# ADS1298-breakout.net
KiCad netlist of a schematic drawn in EAGLE
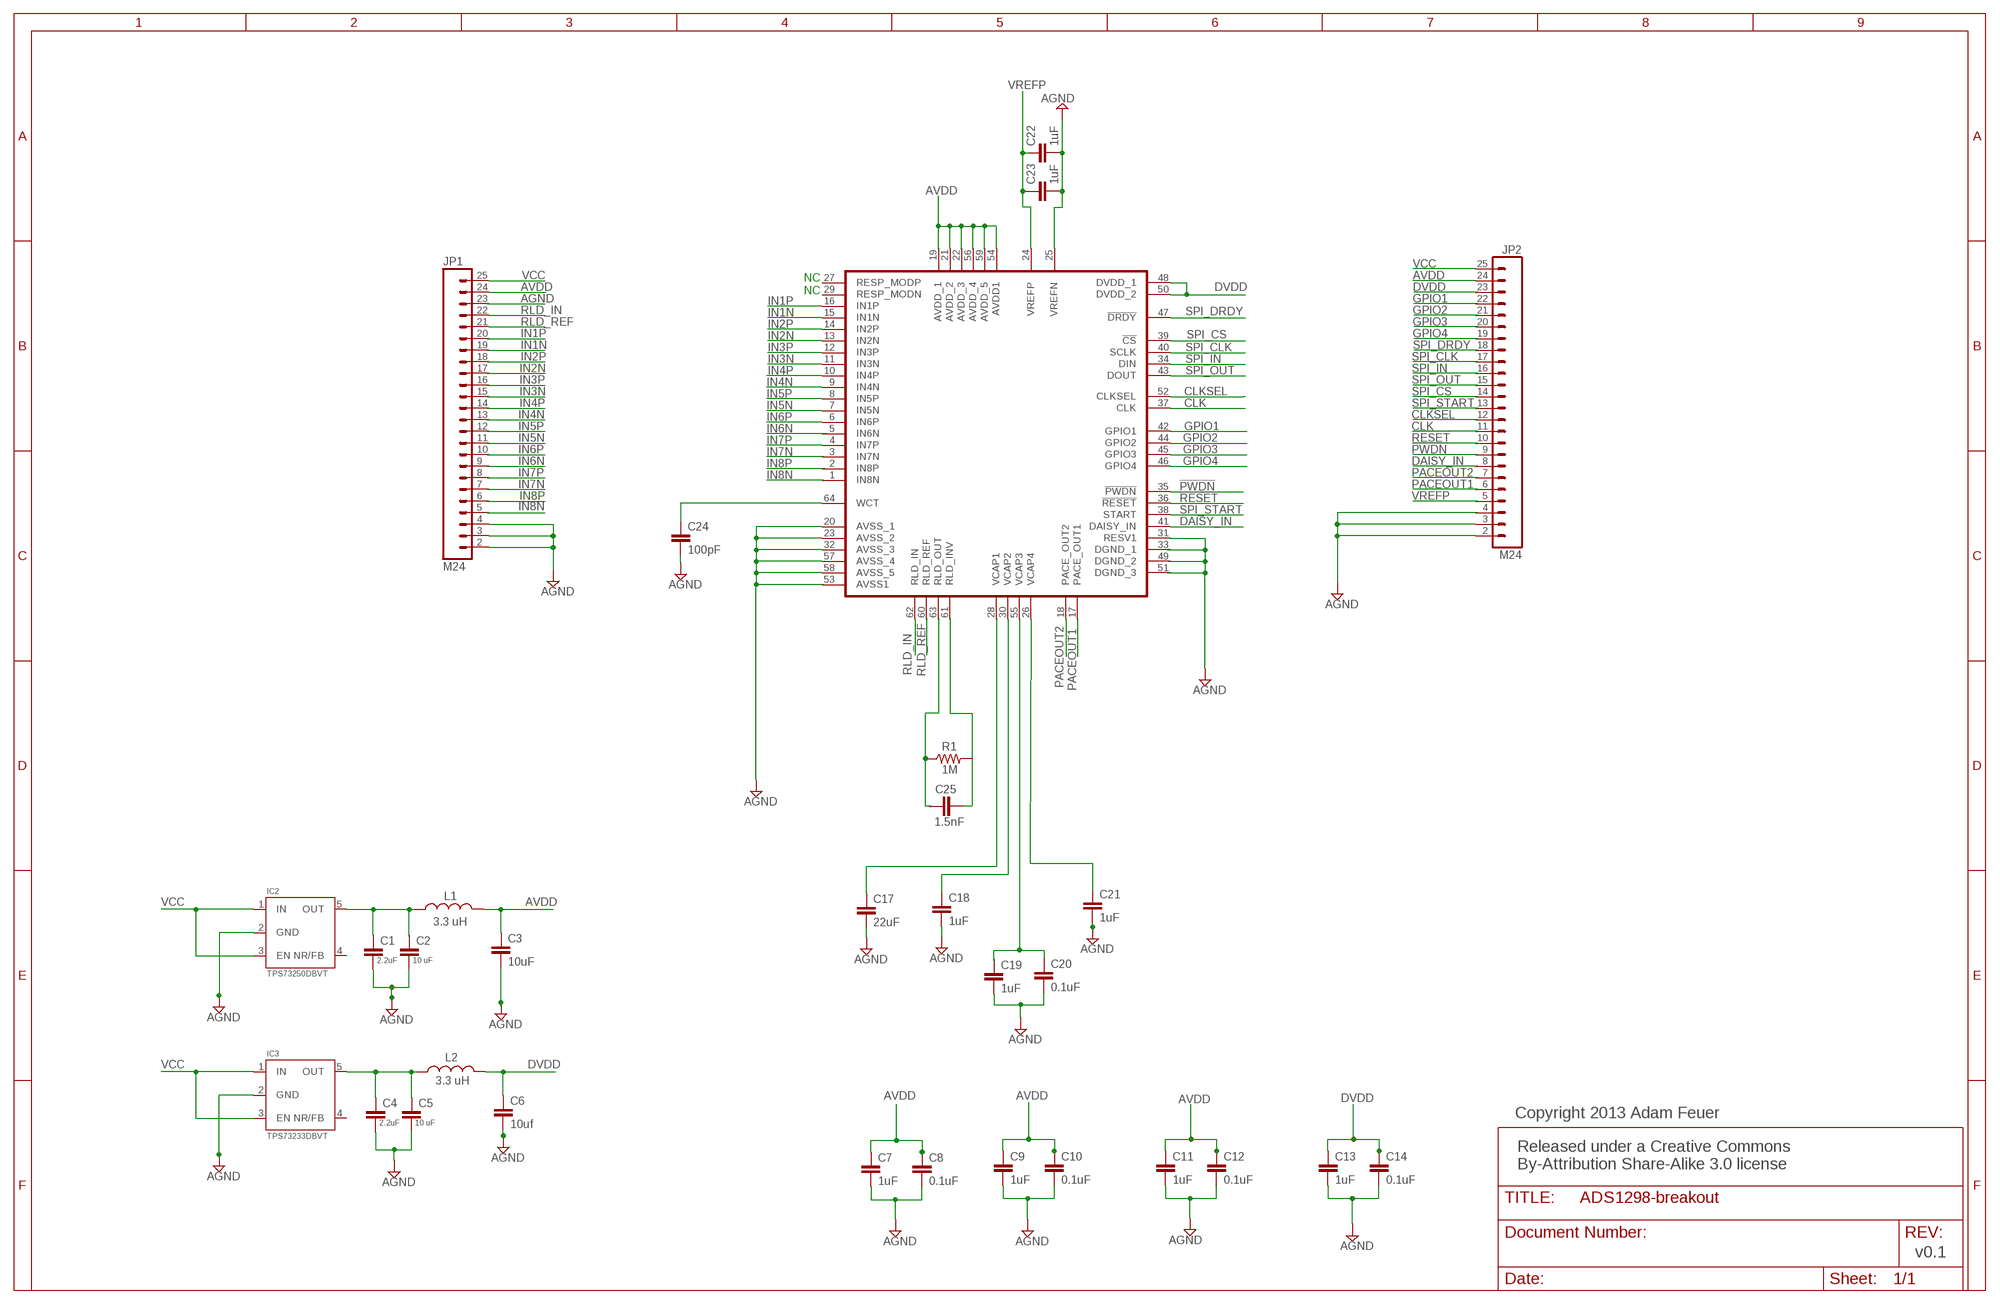
[diagram p0: schematic, sheet 1]

(export (version "E")
  (design (tool "Eeschema 10.0.6"))
  (components
    (comp (ref "C1")
      (value "2.2uF")
      (footprint "eagle-import:0603-CAP")
      (libsource (lib "eagle-import") (part "CAP0603-CAP"))
    )
    (comp (ref "C2")
      (value "10 uF")
      (footprint "eagle-import:0603-CAP")
      (libsource (lib "eagle-import") (part "CAP0603-CAP"))
    )
    (comp (ref "C3")
      (value "10uF")
      (footprint "eagle-import:0603-CAP")
      (libsource (lib "eagle-import") (part "CAP0603-CAP"))
    )
    (comp (ref "C4")
      (value "2.2uF")
      (footprint "eagle-import:0603-CAP")
      (libsource (lib "eagle-import") (part "CAP0603-CAP"))
    )
    (comp (ref "C5")
      (value "10 uF")
      (footprint "eagle-import:0603-CAP")
      (libsource (lib "eagle-import") (part "CAP0603-CAP"))
    )
    (comp (ref "C6")
      (value "10uf")
      (footprint "eagle-import:0603-CAP")
      (libsource (lib "eagle-import") (part "CAP0603-CAP"))
    )
    (comp (ref "C7")
      (value "1uF")
      (footprint "eagle-import:0603-CAP")
      (libsource (lib "eagle-import") (part "CAP0603-CAP"))
    )
    (comp (ref "C8")
      (value "0.1uF")
      (footprint "eagle-import:0603-CAP")
      (libsource (lib "eagle-import") (part "CAP0603-CAP"))
    )
    (comp (ref "C9")
      (value "1uF")
      (footprint "eagle-import:0603-CAP")
      (libsource (lib "eagle-import") (part "CAP0603-CAP"))
    )
    (comp (ref "C10")
      (value "0.1uF")
      (footprint "eagle-import:0603-CAP")
      (libsource (lib "eagle-import") (part "CAP0603-CAP"))
    )
    (comp (ref "C11")
      (value "1uF")
      (footprint "eagle-import:0603-CAP")
      (libsource (lib "eagle-import") (part "CAP0603-CAP"))
    )
    (comp (ref "C12")
      (value "0.1uF")
      (footprint "eagle-import:0603-CAP")
      (libsource (lib "eagle-import") (part "CAP0603-CAP"))
    )
    (comp (ref "C13")
      (value "1uF")
      (footprint "eagle-import:0603-CAP")
      (libsource (lib "eagle-import") (part "CAP0603-CAP"))
    )
    (comp (ref "C14")
      (value "0.1uF")
      (footprint "eagle-import:0603-CAP")
      (libsource (lib "eagle-import") (part "CAP0603-CAP"))
    )
    (comp (ref "C17")
      (value "22uF")
      (footprint "eagle-import:0603-CAP")
      (libsource (lib "eagle-import") (part "CAP0603-CAP"))
    )
    (comp (ref "C18")
      (value "1uF")
      (footprint "eagle-import:0603-CAP")
      (libsource (lib "eagle-import") (part "CAP0603-CAP"))
    )
    (comp (ref "C19")
      (value "1uF")
      (footprint "eagle-import:0603-CAP")
      (libsource (lib "eagle-import") (part "CAP0603-CAP"))
    )
    (comp (ref "C20")
      (value "0.1uF")
      (footprint "eagle-import:0603-CAP")
      (libsource (lib "eagle-import") (part "CAP0603-CAP"))
    )
    (comp (ref "C21")
      (value "1uF")
      (footprint "eagle-import:0603-CAP")
      (libsource (lib "eagle-import") (part "CAP0603-CAP"))
    )
    (comp (ref "C22")
      (value "1uF")
      (footprint "eagle-import:0603-CAP")
      (libsource (lib "eagle-import") (part "CAP0603-CAP"))
    )
    (comp (ref "C23")
      (value "1uF")
      (footprint "eagle-import:0603-CAP")
      (libsource (lib "eagle-import") (part "CAP0603-CAP"))
    )
    (comp (ref "C24")
      (value "100pF")
      (footprint "eagle-import:0603-CAP")
      (libsource (lib "eagle-import") (part "CAP0603-CAP"))
    )
    (comp (ref "C25")
      (value "1.5nF")
      (footprint "eagle-import:0603-CAP")
      (libsource (lib "eagle-import") (part "CAP0603-CAP"))
    )
    (comp (ref "IC1")
      (value "ADS1298*PAG*")
      (footprint "eagle-import:TQFP64")
      (libsource (lib "eagle-import") (part "ADS1298PAG"))
    )
    (comp (ref "IC2")
      (value "TPS73250DBVT")
      (footprint "eagle-import:SOT23-5")
      (libsource (lib "eagle-import") (part "TPS732XXDBV"))
    )
    (comp (ref "IC3")
      (value "TPS73233DBVT")
      (footprint "eagle-import:SOT23-5")
      (libsource (lib "eagle-import") (part "TPS732XXDBV"))
    )
    (comp (ref "JP1")
      (value "M24")
      (footprint "eagle-import:1X24")
      (libsource (lib "eagle-import") (part "M24"))
    )
    (comp (ref "JP2")
      (value "M24")
      (footprint "eagle-import:1X24")
      (libsource (lib "eagle-import") (part "M24"))
    )
    (comp (ref "L1")
      (value "3.3 uH")
      (footprint "eagle-import:0603")
      (libsource (lib "eagle-import") (part "INDUCTOR0603"))
    )
    (comp (ref "L2")
      (value "3.3 uH")
      (footprint "eagle-import:0603")
      (libsource (lib "eagle-import") (part "INDUCTOR0603"))
    )
    (comp (ref "R1")
      (value "1M")
      (footprint "eagle-import:0603-RES")
      (libsource (lib "eagle-import") (part "RESISTOR0603-RES"))
    )
  )
  (nets
    (net (code "1") (name "/AVDD") (class "Default")
      (node (ref "C10") (pin "1") (pinfunction "1_1") (pintype "passive"))
      (node (ref "C11") (pin "1") (pinfunction "1_1") (pintype "passive"))
      (node (ref "C12") (pin "1") (pinfunction "1_1") (pintype "passive"))
      (node (ref "C3") (pin "1") (pinfunction "1_1") (pintype "passive"))
      (node (ref "C7") (pin "1") (pinfunction "1_1") (pintype "passive"))
      (node (ref "C8") (pin "1") (pinfunction "1_1") (pintype "passive"))
      (node (ref "C9") (pin "1") (pinfunction "1_1") (pintype "passive"))
      (node (ref "IC1") (pin "19") (pinfunction "AVDD_1_19") (pintype "power_in"))
      (node (ref "IC1") (pin "21") (pinfunction "AVDD_2_21") (pintype "power_in"))
      (node (ref "IC1") (pin "22") (pinfunction "AVDD_3_22") (pintype "power_in"))
      (node (ref "IC1") (pin "54") (pinfunction "AVDD1_54") (pintype "power_in"))
      (node (ref "IC1") (pin "56") (pinfunction "AVDD_4_56") (pintype "power_in"))
      (node (ref "IC1") (pin "59") (pinfunction "AVDD_5_59") (pintype "power_in"))
      (node (ref "JP1") (pin "24") (pinfunction "24_24") (pintype "passive"))
      (node (ref "JP2") (pin "24") (pinfunction "24_24") (pintype "passive"))
      (node (ref "L1") (pin "2") (pinfunction "2_2") (pintype "passive"))
    )
    (net (code "2") (name "/CLK") (class "Default")
      (node (ref "IC1") (pin "37") (pinfunction "CLK_37") (pintype "input"))
      (node (ref "JP2") (pin "11") (pinfunction "11_11") (pintype "passive"))
    )
    (net (code "3") (name "/CLKSEL") (class "Default")
      (node (ref "IC1") (pin "52") (pinfunction "CLKSEL_52") (pintype "input"))
      (node (ref "JP2") (pin "12") (pinfunction "12_12") (pintype "passive"))
    )
    (net (code "4") (name "/DAISY_IN") (class "Default")
      (node (ref "IC1") (pin "41") (pinfunction "DAISY_IN_41") (pintype "input"))
      (node (ref "JP2") (pin "8") (pinfunction "8_8") (pintype "passive"))
    )
    (net (code "5") (name "/DVDD") (class "Default")
      (node (ref "C13") (pin "1") (pinfunction "1_1") (pintype "passive"))
      (node (ref "C14") (pin "1") (pinfunction "1_1") (pintype "passive"))
      (node (ref "C6") (pin "1") (pinfunction "1_1") (pintype "passive"))
      (node (ref "IC1") (pin "48") (pinfunction "DVDD_1_48") (pintype "power_in"))
      (node (ref "IC1") (pin "50") (pinfunction "DVDD_2_50") (pintype "power_in"))
      (node (ref "JP2") (pin "23") (pinfunction "23_23") (pintype "passive"))
      (node (ref "L2") (pin "2") (pinfunction "2_2") (pintype "passive"))
    )
    (net (code "6") (name "/GPIO1") (class "Default")
      (node (ref "IC1") (pin "42") (pinfunction "GPIO1_42") (pintype "bidirectional"))
      (node (ref "JP2") (pin "22") (pinfunction "22_22") (pintype "passive"))
    )
    (net (code "7") (name "/GPIO2") (class "Default")
      (node (ref "IC1") (pin "44") (pinfunction "GPIO2_44") (pintype "bidirectional"))
      (node (ref "JP2") (pin "21") (pinfunction "21_21") (pintype "passive"))
    )
    (net (code "8") (name "/GPIO3") (class "Default")
      (node (ref "IC1") (pin "45") (pinfunction "GPIO3_45") (pintype "bidirectional"))
      (node (ref "JP2") (pin "20") (pinfunction "20_20") (pintype "passive"))
    )
    (net (code "9") (name "/GPIO4") (class "Default")
      (node (ref "IC1") (pin "46") (pinfunction "GPIO4_46") (pintype "bidirectional"))
      (node (ref "JP2") (pin "19") (pinfunction "19_19") (pintype "passive"))
    )
    (net (code "10") (name "/IN1N") (class "Default")
      (node (ref "IC1") (pin "15") (pinfunction "IN1N_15") (pintype "input"))
      (node (ref "JP1") (pin "19") (pinfunction "19_19") (pintype "passive"))
    )
    (net (code "11") (name "/IN1P") (class "Default")
      (node (ref "IC1") (pin "16") (pinfunction "IN1P_16") (pintype "input"))
      (node (ref "JP1") (pin "20") (pinfunction "20_20") (pintype "passive"))
    )
    (net (code "12") (name "/IN2N") (class "Default")
      (node (ref "IC1") (pin "13") (pinfunction "IN2N_13") (pintype "input"))
      (node (ref "JP1") (pin "17") (pinfunction "17_17") (pintype "passive"))
    )
    (net (code "13") (name "/IN2P") (class "Default")
      (node (ref "IC1") (pin "14") (pinfunction "IN2P_14") (pintype "input"))
      (node (ref "JP1") (pin "18") (pinfunction "18_18") (pintype "passive"))
    )
    (net (code "14") (name "/IN3N") (class "Default")
      (node (ref "IC1") (pin "11") (pinfunction "IN3N_11") (pintype "input"))
      (node (ref "JP1") (pin "15") (pinfunction "15_15") (pintype "passive"))
    )
    (net (code "15") (name "/IN3P") (class "Default")
      (node (ref "IC1") (pin "12") (pinfunction "IN3P_12") (pintype "input"))
      (node (ref "JP1") (pin "16") (pinfunction "16_16") (pintype "passive"))
    )
    (net (code "16") (name "/IN4N") (class "Default")
      (node (ref "IC1") (pin "9") (pinfunction "IN4N_9") (pintype "input"))
      (node (ref "JP1") (pin "13") (pinfunction "13_13") (pintype "passive"))
    )
    (net (code "17") (name "/IN4P") (class "Default")
      (node (ref "IC1") (pin "10") (pinfunction "IN4P_10") (pintype "input"))
      (node (ref "JP1") (pin "14") (pinfunction "14_14") (pintype "passive"))
    )
    (net (code "18") (name "/IN5N") (class "Default")
      (node (ref "IC1") (pin "7") (pinfunction "IN5N_7") (pintype "input"))
      (node (ref "JP1") (pin "11") (pinfunction "11_11") (pintype "passive"))
    )
    (net (code "19") (name "/IN5P") (class "Default")
      (node (ref "IC1") (pin "8") (pinfunction "IN5P_8") (pintype "input"))
      (node (ref "JP1") (pin "12") (pinfunction "12_12") (pintype "passive"))
    )
    (net (code "20") (name "/IN6N") (class "Default")
      (node (ref "IC1") (pin "5") (pinfunction "IN6N_5") (pintype "input"))
      (node (ref "JP1") (pin "9") (pinfunction "9_9") (pintype "passive"))
    )
    (net (code "21") (name "/IN6P") (class "Default")
      (node (ref "IC1") (pin "6") (pinfunction "IN6P_6") (pintype "input"))
      (node (ref "JP1") (pin "10") (pinfunction "10_10") (pintype "passive"))
    )
    (net (code "22") (name "/IN7N") (class "Default")
      (node (ref "IC1") (pin "3") (pinfunction "IN7N_3") (pintype "input"))
      (node (ref "JP1") (pin "7") (pinfunction "7_7") (pintype "passive"))
    )
    (net (code "23") (name "/IN7P") (class "Default")
      (node (ref "IC1") (pin "4") (pinfunction "IN7P_4") (pintype "input"))
      (node (ref "JP1") (pin "8") (pinfunction "8_8") (pintype "passive"))
    )
    (net (code "24") (name "/IN8N") (class "Default")
      (node (ref "IC1") (pin "1") (pinfunction "IN8N_1") (pintype "input"))
      (node (ref "JP1") (pin "5") (pinfunction "5_5") (pintype "passive"))
    )
    (net (code "25") (name "/IN8P") (class "Default")
      (node (ref "IC1") (pin "2") (pinfunction "IN8P_2") (pintype "input"))
      (node (ref "JP1") (pin "6") (pinfunction "6_6") (pintype "passive"))
    )
    (net (code "26") (name "/PACEOUT1") (class "Default")
      (node (ref "IC1") (pin "17") (pinfunction "PACE_OUT1_17") (pintype "output"))
      (node (ref "JP2") (pin "6") (pinfunction "6_6") (pintype "passive"))
    )
    (net (code "27") (name "/PACEOUT2") (class "Default")
      (node (ref "IC1") (pin "18") (pinfunction "PACE_OUT2_18") (pintype "output"))
      (node (ref "JP2") (pin "7") (pinfunction "7_7") (pintype "passive"))
    )
    (net (code "28") (name "/RLD_IN") (class "Default")
      (node (ref "IC1") (pin "62") (pinfunction "RLD_IN_62") (pintype "input"))
      (node (ref "JP1") (pin "22") (pinfunction "22_22") (pintype "passive"))
    )
    (net (code "29") (name "/RLD_REF") (class "Default")
      (node (ref "IC1") (pin "60") (pinfunction "RLD_REF_60") (pintype "input"))
      (node (ref "JP1") (pin "21") (pinfunction "21_21") (pintype "passive"))
    )
    (net (code "30") (name "/SPI_CLK") (class "Default")
      (node (ref "IC1") (pin "40") (pinfunction "SCLK_40") (pintype "input"))
      (node (ref "JP2") (pin "17") (pinfunction "17_17") (pintype "passive"))
    )
    (net (code "31") (name "/SPI_CS") (class "Default")
      (node (ref "IC1") (pin "39") (pinfunction "~{CS}_39") (pintype "input"))
      (node (ref "JP2") (pin "14") (pinfunction "14_14") (pintype "passive"))
    )
    (net (code "32") (name "/SPI_DRDY") (class "Default")
      (node (ref "IC1") (pin "47") (pinfunction "~{DRDY}_47") (pintype "output"))
      (node (ref "JP2") (pin "18") (pinfunction "18_18") (pintype "passive"))
    )
    (net (code "33") (name "/SPI_IN") (class "Default")
      (node (ref "IC1") (pin "34") (pinfunction "DIN_34") (pintype "input"))
      (node (ref "JP2") (pin "16") (pinfunction "16_16") (pintype "passive"))
    )
    (net (code "34") (name "/SPI_OUT") (class "Default")
      (node (ref "IC1") (pin "43") (pinfunction "DOUT_43") (pintype "output"))
      (node (ref "JP2") (pin "15") (pinfunction "15_15") (pintype "passive"))
    )
    (net (code "35") (name "/SPI_START") (class "Default")
      (node (ref "IC1") (pin "38") (pinfunction "START_38") (pintype "input"))
      (node (ref "JP2") (pin "13") (pinfunction "13_13") (pintype "passive"))
    )
    (net (code "36") (name "/VCC") (class "Default")
      (node (ref "IC2") (pin "1") (pinfunction "IN_1") (pintype "bidirectional"))
      (node (ref "IC2") (pin "3") (pinfunction "EN_3") (pintype "bidirectional"))
      (node (ref "IC3") (pin "1") (pinfunction "IN_1") (pintype "bidirectional"))
      (node (ref "IC3") (pin "3") (pinfunction "EN_3") (pintype "bidirectional"))
      (node (ref "JP1") (pin "25") (pinfunction "25_25") (pintype "passive"))
      (node (ref "JP2") (pin "25") (pinfunction "25_25") (pintype "passive"))
    )
    (net (code "37") (name "/VREFP") (class "Default")
      (node (ref "C22") (pin "1") (pinfunction "1_1") (pintype "passive"))
      (node (ref "C23") (pin "1") (pinfunction "1_1") (pintype "passive"))
      (node (ref "IC1") (pin "24") (pinfunction "VREFP_24") (pintype "bidirectional"))
      (node (ref "JP2") (pin "5") (pinfunction "5_5") (pintype "passive"))
    )
    (net (code "38") (name "/~{PWDN}") (class "Default")
      (node (ref "IC1") (pin "35") (pinfunction "~{PWDN}_35") (pintype "input"))
      (node (ref "JP2") (pin "9") (pinfunction "9_9") (pintype "passive"))
    )
    (net (code "39") (name "/~{RESET}") (class "Default")
      (node (ref "IC1") (pin "36") (pinfunction "~{RESET}_36") (pintype "input"))
      (node (ref "JP2") (pin "10") (pinfunction "10_10") (pintype "passive"))
    )
    (net (code "40") (name "AGND") (class "Default")
      (node (ref "C1") (pin "2") (pinfunction "2_2") (pintype "passive"))
      (node (ref "C10") (pin "2") (pinfunction "2_2") (pintype "passive"))
      (node (ref "C11") (pin "2") (pinfunction "2_2") (pintype "passive"))
      (node (ref "C12") (pin "2") (pinfunction "2_2") (pintype "passive"))
      (node (ref "C13") (pin "2") (pinfunction "2_2") (pintype "passive"))
      (node (ref "C14") (pin "2") (pinfunction "2_2") (pintype "passive"))
      (node (ref "C17") (pin "2") (pinfunction "2_2") (pintype "passive"))
      (node (ref "C18") (pin "2") (pinfunction "2_2") (pintype "passive"))
      (node (ref "C19") (pin "2") (pinfunction "2_2") (pintype "passive"))
      (node (ref "C2") (pin "2") (pinfunction "2_2") (pintype "passive"))
      (node (ref "C20") (pin "2") (pinfunction "2_2") (pintype "passive"))
      (node (ref "C21") (pin "2") (pinfunction "2_2") (pintype "passive"))
      (node (ref "C22") (pin "2") (pinfunction "2_2") (pintype "passive"))
      (node (ref "C23") (pin "2") (pinfunction "2_2") (pintype "passive"))
      (node (ref "C24") (pin "2") (pinfunction "2_2") (pintype "passive"))
      (node (ref "C3") (pin "2") (pinfunction "2_2") (pintype "passive"))
      (node (ref "C4") (pin "2") (pinfunction "2_2") (pintype "passive"))
      (node (ref "C5") (pin "2") (pinfunction "2_2") (pintype "passive"))
      (node (ref "C6") (pin "2") (pinfunction "2_2") (pintype "passive"))
      (node (ref "C7") (pin "2") (pinfunction "2_2") (pintype "passive"))
      (node (ref "C8") (pin "2") (pinfunction "2_2") (pintype "passive"))
      (node (ref "C9") (pin "2") (pinfunction "2_2") (pintype "passive"))
      (node (ref "IC1") (pin "20") (pinfunction "AVSS_1_20") (pintype "power_in"))
      (node (ref "IC1") (pin "23") (pinfunction "AVSS_2_23") (pintype "power_in"))
      (node (ref "IC1") (pin "25") (pinfunction "VREFN_25") (pintype "bidirectional"))
      (node (ref "IC1") (pin "31") (pinfunction "RESV1_31") (pintype "input"))
      (node (ref "IC1") (pin "32") (pinfunction "AVSS_3_32") (pintype "power_in"))
      (node (ref "IC1") (pin "33") (pinfunction "DGND_1_33") (pintype "power_in"))
      (node (ref "IC1") (pin "49") (pinfunction "DGND_2_49") (pintype "power_in"))
      (node (ref "IC1") (pin "51") (pinfunction "DGND_3_51") (pintype "power_in"))
      (node (ref "IC1") (pin "53") (pinfunction "AVSS1_53") (pintype "power_in"))
      (node (ref "IC1") (pin "57") (pinfunction "AVSS_4_57") (pintype "power_in"))
      (node (ref "IC1") (pin "58") (pinfunction "AVSS_5_58") (pintype "power_in"))
      (node (ref "IC2") (pin "2") (pinfunction "GND_2") (pintype "bidirectional"))
      (node (ref "IC3") (pin "2") (pinfunction "GND_2") (pintype "bidirectional"))
      (node (ref "JP1") (pin "2") (pinfunction "2_2") (pintype "passive"))
      (node (ref "JP1") (pin "23") (pinfunction "23_23") (pintype "passive"))
      (node (ref "JP1") (pin "3") (pinfunction "3_3") (pintype "passive"))
      (node (ref "JP1") (pin "4") (pinfunction "4_4") (pintype "passive"))
      (node (ref "JP2") (pin "2") (pinfunction "2_2") (pintype "passive"))
      (node (ref "JP2") (pin "3") (pinfunction "3_3") (pintype "passive"))
      (node (ref "JP2") (pin "4") (pinfunction "4_4") (pintype "passive"))
    )
    (net (code "41") (name "Net-(IC1-RLD_INV)") (class "Default")
      (node (ref "C25") (pin "2") (pinfunction "2_2") (pintype "passive"))
      (node (ref "IC1") (pin "61") (pinfunction "RLD_INV_61") (pintype "bidirectional"))
      (node (ref "R1") (pin "2") (pinfunction "2_2") (pintype "passive"))
    )
    (net (code "42") (name "Net-(IC1-RLD_OUT)") (class "Default")
      (node (ref "C25") (pin "1") (pinfunction "1_1") (pintype "passive"))
      (node (ref "IC1") (pin "63") (pinfunction "RLD_OUT_63") (pintype "output"))
      (node (ref "R1") (pin "1") (pinfunction "1_1") (pintype "passive"))
    )
    (net (code "43") (name "Net-(IC1-VCAP1)") (class "Default")
      (node (ref "C17") (pin "1") (pinfunction "1_1") (pintype "passive"))
      (node (ref "IC1") (pin "28") (pinfunction "VCAP1_28") (pintype "bidirectional"))
    )
    (net (code "44") (name "Net-(IC1-VCAP2)") (class "Default")
      (node (ref "C18") (pin "1") (pinfunction "1_1") (pintype "passive"))
      (node (ref "IC1") (pin "30") (pinfunction "VCAP2_30") (pintype "bidirectional"))
    )
    (net (code "45") (name "Net-(IC1-VCAP3)") (class "Default")
      (node (ref "C19") (pin "1") (pinfunction "1_1") (pintype "passive"))
      (node (ref "C20") (pin "1") (pinfunction "1_1") (pintype "passive"))
      (node (ref "IC1") (pin "55") (pinfunction "VCAP3_55") (pintype "bidirectional"))
    )
    (net (code "46") (name "Net-(IC1-VCAP4)") (class "Default")
      (node (ref "C21") (pin "1") (pinfunction "1_1") (pintype "passive"))
      (node (ref "IC1") (pin "26") (pinfunction "VCAP4_26") (pintype "bidirectional"))
    )
    (net (code "47") (name "Net-(IC1-WCT)") (class "Default")
      (node (ref "C24") (pin "1") (pinfunction "1_1") (pintype "passive"))
      (node (ref "IC1") (pin "64") (pinfunction "WCT_64") (pintype "output"))
    )
    (net (code "48") (name "Net-(IC2-OUT)") (class "Default")
      (node (ref "C1") (pin "1") (pinfunction "1_1") (pintype "passive"))
      (node (ref "C2") (pin "1") (pinfunction "1_1") (pintype "passive"))
      (node (ref "IC2") (pin "5") (pinfunction "OUT_5") (pintype "bidirectional"))
      (node (ref "L1") (pin "1") (pinfunction "1_1") (pintype "passive"))
    )
    (net (code "49") (name "Net-(IC3-OUT)") (class "Default")
      (node (ref "C4") (pin "1") (pinfunction "1_1") (pintype "passive"))
      (node (ref "C5") (pin "1") (pinfunction "1_1") (pintype "passive"))
      (node (ref "IC3") (pin "5") (pinfunction "OUT_5") (pintype "bidirectional"))
      (node (ref "L2") (pin "1") (pinfunction "1_1") (pintype "passive"))
    )
    (net (code "50") (name "unconnected-(IC1-RESP_MODN-Pad29)") (class "Default")
      (node (ref "IC1") (pin "29") (pinfunction "RESP_MODN_29") (pintype "output"))
    )
    (net (code "51") (name "unconnected-(IC1-RESP_MODP-Pad27)") (class "Default")
      (node (ref "IC1") (pin "27") (pinfunction "RESP_MODP_27") (pintype "output"))
    )
    (net (code "52") (name "unconnected-(IC2-NR{slash}FB-Pad4)") (class "Default")
      (node (ref "IC2") (pin "4") (pinfunction "NR/FB_4") (pintype "bidirectional"))
    )
    (net (code "53") (name "unconnected-(IC3-NR{slash}FB-Pad4)") (class "Default")
      (node (ref "IC3") (pin "4") (pinfunction "NR/FB_4") (pintype "bidirectional"))
    )
  )
)
